# BMS.net
KiCad netlist of a schematic drawn in EAGLE
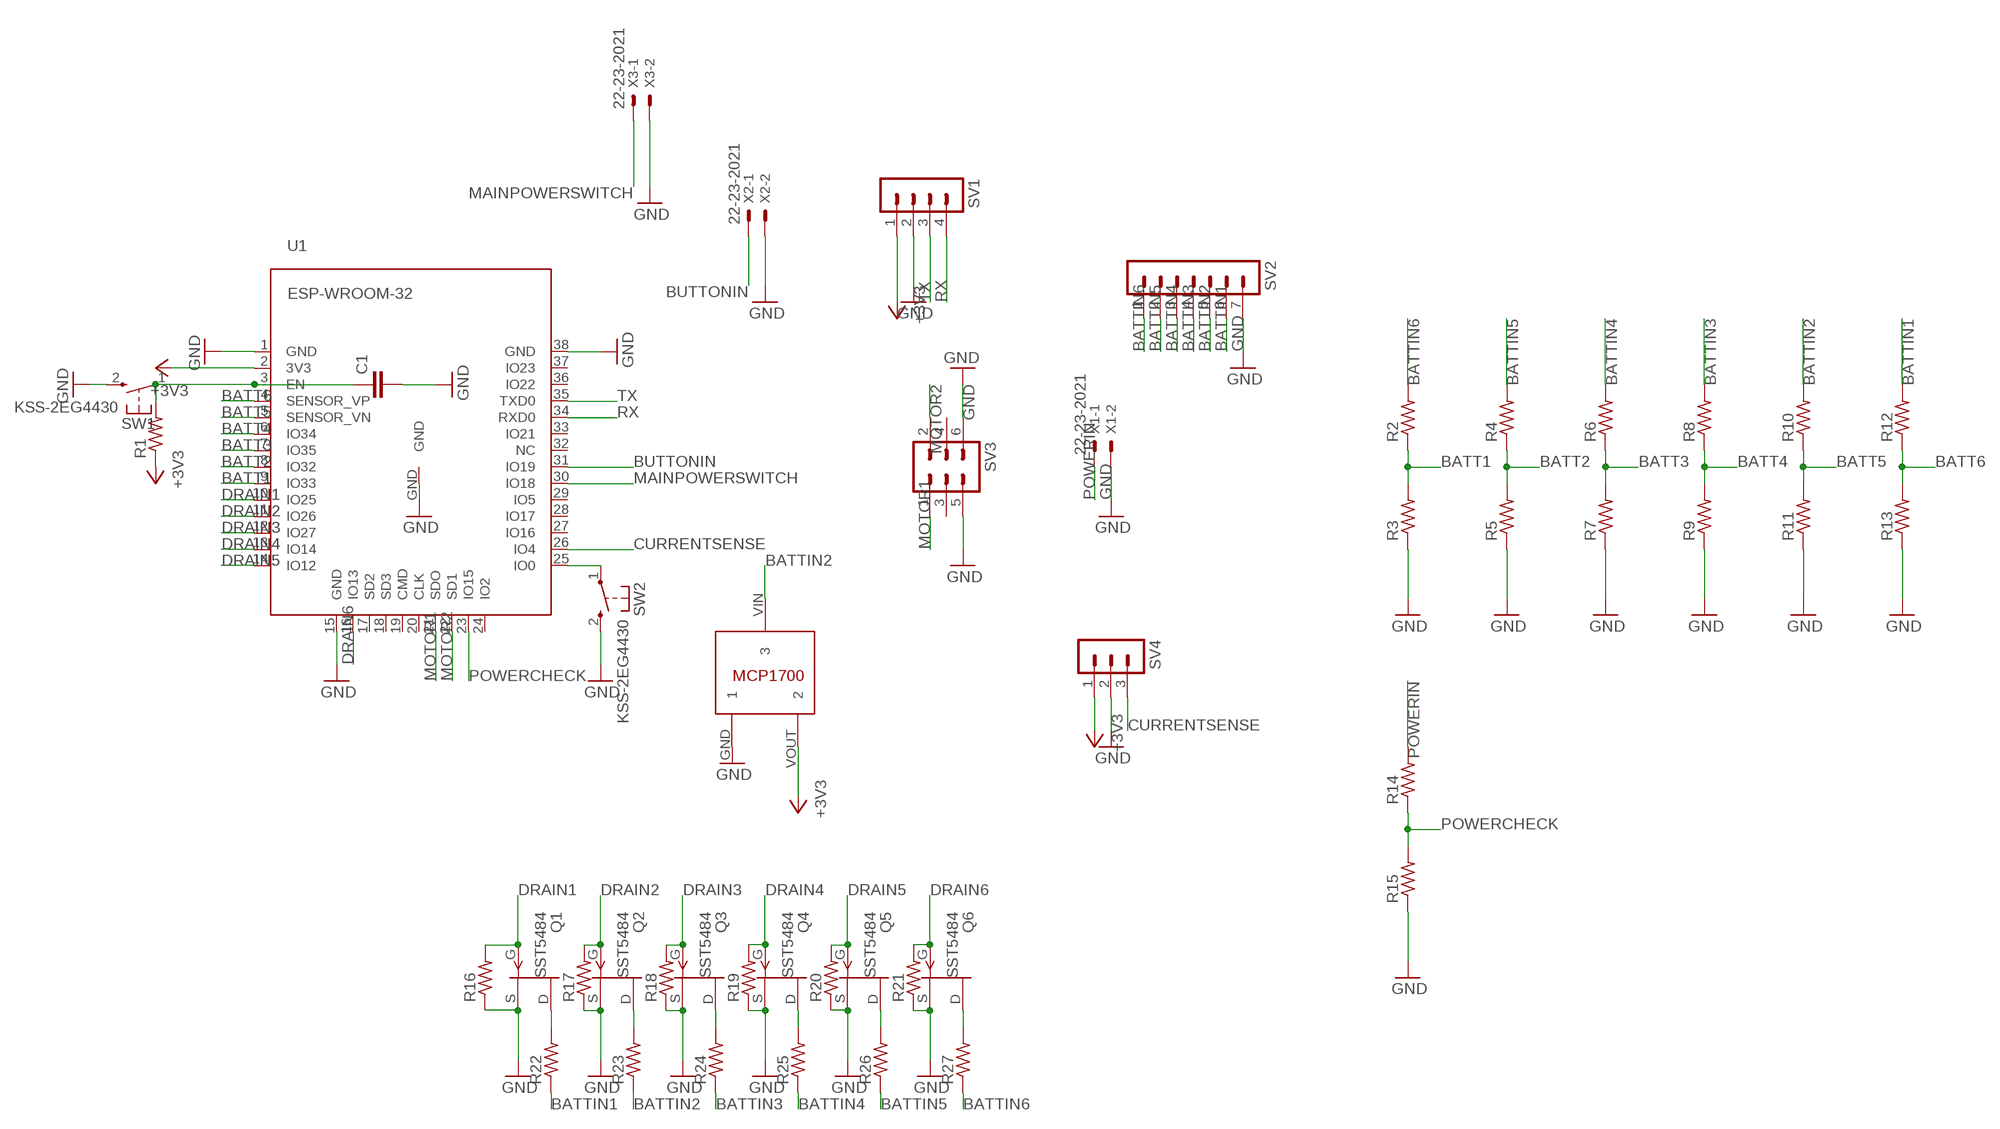
[diagram p0: schematic, sheet 1]

(export (version "E")
  (design (tool "Eeschema 10.0.6"))
  (components
    (comp (ref "C1")
      (value "C-EUC0402")
      (footprint "eagle-import:C0402")
      (libsource (lib "eagle-import") (part "C-EUC0402"))
    )
    (comp (ref "Q1")
      (value "SST5484")
      (footprint "eagle-import:SOT23")
      (libsource (lib "eagle-import") (part "?548SST4"))
    )
    (comp (ref "Q2")
      (value "SST5484")
      (footprint "eagle-import:SOT23")
      (libsource (lib "eagle-import") (part "?548SST4"))
    )
    (comp (ref "Q3")
      (value "SST5484")
      (footprint "eagle-import:SOT23")
      (libsource (lib "eagle-import") (part "?548SST4"))
    )
    (comp (ref "Q4")
      (value "SST5484")
      (footprint "eagle-import:SOT23")
      (libsource (lib "eagle-import") (part "?548SST4"))
    )
    (comp (ref "Q5")
      (value "SST5484")
      (footprint "eagle-import:SOT23")
      (libsource (lib "eagle-import") (part "?548SST4"))
    )
    (comp (ref "Q6")
      (value "SST5484")
      (footprint "eagle-import:SOT23")
      (libsource (lib "eagle-import") (part "?548SST4"))
    )
    (comp (ref "R1")
      (value "R-US_R0805")
      (footprint "eagle-import:R0805")
      (libsource (lib "eagle-import") (part "R-US_R0805"))
    )
    (comp (ref "R2")
      (value "R-US_M0805")
      (footprint "eagle-import:M0805")
      (libsource (lib "eagle-import") (part "resistor_348_R-US_M0805"))
    )
    (comp (ref "R3")
      (value "R-US_M0805")
      (footprint "eagle-import:M0805")
      (libsource (lib "eagle-import") (part "resistor_348_R-US_M0805"))
    )
    (comp (ref "R4")
      (value "R-US_M0805")
      (footprint "eagle-import:M0805")
      (libsource (lib "eagle-import") (part "resistor_348_R-US_M0805"))
    )
    (comp (ref "R5")
      (value "R-US_M0805")
      (footprint "eagle-import:M0805")
      (libsource (lib "eagle-import") (part "resistor_348_R-US_M0805"))
    )
    (comp (ref "R6")
      (value "R-US_M0805")
      (footprint "eagle-import:M0805")
      (libsource (lib "eagle-import") (part "resistor_348_R-US_M0805"))
    )
    (comp (ref "R7")
      (value "R-US_M0805")
      (footprint "eagle-import:M0805")
      (libsource (lib "eagle-import") (part "resistor_348_R-US_M0805"))
    )
    (comp (ref "R8")
      (value "R-US_M0805")
      (footprint "eagle-import:M0805")
      (libsource (lib "eagle-import") (part "resistor_348_R-US_M0805"))
    )
    (comp (ref "R9")
      (value "R-US_M0805")
      (footprint "eagle-import:M0805")
      (libsource (lib "eagle-import") (part "resistor_348_R-US_M0805"))
    )
    (comp (ref "R10")
      (value "R-US_M0805")
      (footprint "eagle-import:M0805")
      (libsource (lib "eagle-import") (part "resistor_348_R-US_M0805"))
    )
    (comp (ref "R11")
      (value "R-US_M0805")
      (footprint "eagle-import:M0805")
      (libsource (lib "eagle-import") (part "resistor_348_R-US_M0805"))
    )
    (comp (ref "R12")
      (value "R-US_M0805")
      (footprint "eagle-import:M0805")
      (libsource (lib "eagle-import") (part "resistor_348_R-US_M0805"))
    )
    (comp (ref "R13")
      (value "R-US_M0805")
      (footprint "eagle-import:M0805")
      (libsource (lib "eagle-import") (part "resistor_348_R-US_M0805"))
    )
    (comp (ref "R14")
      (value "R-US_M0805")
      (footprint "eagle-import:M0805")
      (libsource (lib "eagle-import") (part "resistor_348_R-US_M0805"))
    )
    (comp (ref "R15")
      (value "R-US_M0805")
      (footprint "eagle-import:M0805")
      (libsource (lib "eagle-import") (part "resistor_348_R-US_M0805"))
    )
    (comp (ref "R16")
      (value "R-US_M0805")
      (footprint "eagle-import:M0805")
      (libsource (lib "eagle-import") (part "R-US_M0805"))
    )
    (comp (ref "R17")
      (value "R-US_M0805")
      (footprint "eagle-import:M0805")
      (libsource (lib "eagle-import") (part "R-US_M0805"))
    )
    (comp (ref "R18")
      (value "R-US_M0805")
      (footprint "eagle-import:M0805")
      (libsource (lib "eagle-import") (part "R-US_M0805"))
    )
    (comp (ref "R19")
      (value "R-US_M0805")
      (footprint "eagle-import:M0805")
      (libsource (lib "eagle-import") (part "R-US_M0805"))
    )
    (comp (ref "R20")
      (value "R-US_M0805")
      (footprint "eagle-import:M0805")
      (libsource (lib "eagle-import") (part "R-US_M0805"))
    )
    (comp (ref "R21")
      (value "R-US_M0805")
      (footprint "eagle-import:M0805")
      (libsource (lib "eagle-import") (part "R-US_M0805"))
    )
    (comp (ref "R22")
      (value "R-US_M0805")
      (footprint "eagle-import:M0805")
      (libsource (lib "eagle-import") (part "R-US_M0805"))
    )
    (comp (ref "R23")
      (value "R-US_M0805")
      (footprint "eagle-import:M0805")
      (libsource (lib "eagle-import") (part "R-US_M0805"))
    )
    (comp (ref "R24")
      (value "R-US_M0805")
      (footprint "eagle-import:M0805")
      (libsource (lib "eagle-import") (part "R-US_M0805"))
    )
    (comp (ref "R25")
      (value "R-US_M0805")
      (footprint "eagle-import:M0805")
      (libsource (lib "eagle-import") (part "R-US_M0805"))
    )
    (comp (ref "R26")
      (value "R-US_M0805")
      (footprint "eagle-import:M0805")
      (libsource (lib "eagle-import") (part "R-US_M0805"))
    )
    (comp (ref "R27")
      (value "R-US_M0805")
      (footprint "eagle-import:M0805")
      (libsource (lib "eagle-import") (part "R-US_M0805"))
    )
    (comp (ref "SV1")
      (value "MA04-1")
      (footprint "eagle-import:MA04-1")
      (libsource (lib "eagle-import") (part "MA04-1"))
    )
    (comp (ref "SV2")
      (value "MA07-1")
      (footprint "eagle-import:MA07-1")
      (libsource (lib "eagle-import") (part "MA07-1"))
    )
    (comp (ref "SV3")
      (value "MA03-2")
      (footprint "eagle-import:MA03-2")
      (libsource (lib "eagle-import") (part "MA03-2"))
    )
    (comp (ref "SV4")
      (value "MA03-1")
      (footprint "eagle-import:MA03-1")
      (libsource (lib "eagle-import") (part "MA03-1"))
    )
    (comp (ref "SW1")
      (value "KSS-2EG4430")
      (footprint "eagle-import:KSS-2EG4430")
      (libsource (lib "eagle-import") (part "KSS-2EG4430"))
    )
    (comp (ref "SW2")
      (value "KSS-2EG4430")
      (footprint "eagle-import:KSS-2EG4430")
      (libsource (lib "eagle-import") (part "KSS-2EG4430"))
    )
    (comp (ref "U$1")
      (value "MCP1700T-3302E/TT")
      (footprint "eagle-import:MCP1700T-3302E_TT")
      (libsource (lib "eagle-import") (part "MCP1700T-3302E/TT"))
    )
    (comp (ref "U1")
      (value "ESP-WROOM-32")
      (footprint "eagle-import:ESP-WROOM-32")
      (libsource (lib "eagle-import") (part "ESP-WROOM-32"))
    )
    (comp (ref "X1")
      (value "22-23-2021")
      (footprint "eagle-import:22-23-2021")
      (fields (field (name "MF") "MOLEX"))
      (libsource (lib "eagle-import") (part "22-23-2021"))
    )
    (comp (ref "X2")
      (value "22-23-2021")
      (footprint "eagle-import:22-23-2021")
      (fields (field (name "MF") "MOLEX"))
      (libsource (lib "eagle-import") (part "22-23-2021"))
    )
    (comp (ref "X3")
      (value "22-23-2021")
      (footprint "eagle-import:22-23-2021")
      (fields (field (name "MF") "MOLEX"))
      (libsource (lib "eagle-import") (part "22-23-2021"))
    )
  )
  (nets
    (net (code "1") (name "+3V3") (class "Default")
      (node (ref "R1") (pin "1") (pinfunction "1_1") (pintype "passive"))
      (node (ref "SV1") (pin "1") (pinfunction "1_1") (pintype "passive"))
      (node (ref "SV4") (pin "1") (pinfunction "1_1") (pintype "passive"))
      (node (ref "U$1") (pin "VOUT") (pinfunction "2_VOUT") (pintype "bidirectional"))
      (node (ref "U1") (pin "2") (pinfunction "3V3_2") (pintype "bidirectional"))
    )
    (net (code "2") (name "/BATT1") (class "Default")
      (node (ref "R2") (pin "1") (pinfunction "1_1") (pintype "passive"))
      (node (ref "R3") (pin "2") (pinfunction "2_2") (pintype "passive"))
      (node (ref "U1") (pin "9") (pinfunction "IO33_9") (pintype "bidirectional"))
    )
    (net (code "3") (name "/BATT2") (class "Default")
      (node (ref "R4") (pin "1") (pinfunction "1_1") (pintype "passive"))
      (node (ref "R5") (pin "2") (pinfunction "2_2") (pintype "passive"))
      (node (ref "U1") (pin "8") (pinfunction "IO32_8") (pintype "bidirectional"))
    )
    (net (code "4") (name "/BATT3") (class "Default")
      (node (ref "R6") (pin "1") (pinfunction "1_1") (pintype "passive"))
      (node (ref "R7") (pin "2") (pinfunction "2_2") (pintype "passive"))
      (node (ref "U1") (pin "7") (pinfunction "IO35_7") (pintype "bidirectional"))
    )
    (net (code "5") (name "/BATT4") (class "Default")
      (node (ref "R8") (pin "1") (pinfunction "1_1") (pintype "passive"))
      (node (ref "R9") (pin "2") (pinfunction "2_2") (pintype "passive"))
      (node (ref "U1") (pin "6") (pinfunction "IO34_6") (pintype "bidirectional"))
    )
    (net (code "6") (name "/BATT5") (class "Default")
      (node (ref "R10") (pin "1") (pinfunction "1_1") (pintype "passive"))
      (node (ref "R11") (pin "2") (pinfunction "2_2") (pintype "passive"))
      (node (ref "U1") (pin "5") (pinfunction "SENSOR_VN_5") (pintype "bidirectional"))
    )
    (net (code "7") (name "/BATT6") (class "Default")
      (node (ref "R12") (pin "1") (pinfunction "1_1") (pintype "passive"))
      (node (ref "R13") (pin "2") (pinfunction "2_2") (pintype "passive"))
      (node (ref "U1") (pin "4") (pinfunction "SENSOR_VP_4") (pintype "bidirectional"))
    )
    (net (code "8") (name "/BATTIN1") (class "Default")
      (node (ref "R12") (pin "2") (pinfunction "2_2") (pintype "passive"))
      (node (ref "R22") (pin "1") (pinfunction "1_1") (pintype "passive"))
      (node (ref "SV2") (pin "6") (pinfunction "6_6") (pintype "passive"))
    )
    (net (code "9") (name "/BATTIN2") (class "Default")
      (node (ref "R10") (pin "2") (pinfunction "2_2") (pintype "passive"))
      (node (ref "R23") (pin "1") (pinfunction "1_1") (pintype "passive"))
      (node (ref "SV2") (pin "5") (pinfunction "5_5") (pintype "passive"))
      (node (ref "U$1") (pin "VIN") (pinfunction "3_VIN") (pintype "bidirectional"))
    )
    (net (code "10") (name "/BATTIN3") (class "Default")
      (node (ref "R24") (pin "1") (pinfunction "1_1") (pintype "passive"))
      (node (ref "R8") (pin "2") (pinfunction "2_2") (pintype "passive"))
      (node (ref "SV2") (pin "4") (pinfunction "4_4") (pintype "passive"))
    )
    (net (code "11") (name "/BATTIN4") (class "Default")
      (node (ref "R25") (pin "1") (pinfunction "1_1") (pintype "passive"))
      (node (ref "R6") (pin "2") (pinfunction "2_2") (pintype "passive"))
      (node (ref "SV2") (pin "3") (pinfunction "3_3") (pintype "passive"))
    )
    (net (code "12") (name "/BATTIN5") (class "Default")
      (node (ref "R26") (pin "1") (pinfunction "1_1") (pintype "passive"))
      (node (ref "R4") (pin "2") (pinfunction "2_2") (pintype "passive"))
      (node (ref "SV2") (pin "2") (pinfunction "2_2") (pintype "passive"))
    )
    (net (code "13") (name "/BATTIN6") (class "Default")
      (node (ref "R2") (pin "2") (pinfunction "2_2") (pintype "passive"))
      (node (ref "R27") (pin "1") (pinfunction "1_1") (pintype "passive"))
      (node (ref "SV2") (pin "1") (pinfunction "1_1") (pintype "passive"))
    )
    (net (code "14") (name "/BUTTONIN") (class "Default")
      (node (ref "U1") (pin "31") (pinfunction "IO19_31") (pintype "bidirectional"))
      (node (ref "X2") (pin "1") (pinfunction "S_1") (pintype "passive"))
    )
    (net (code "15") (name "/CURRENTSENSE") (class "Default")
      (node (ref "SV4") (pin "3") (pinfunction "3_3") (pintype "passive"))
      (node (ref "U1") (pin "26") (pinfunction "IO4_26") (pintype "bidirectional"))
    )
    (net (code "16") (name "/DRAIN1") (class "Default")
      (node (ref "Q1") (pin "3") (pinfunction "G_3") (pintype "passive"))
      (node (ref "R16") (pin "2") (pinfunction "2_2") (pintype "passive"))
      (node (ref "U1") (pin "10") (pinfunction "IO25_10") (pintype "bidirectional"))
    )
    (net (code "17") (name "/DRAIN2") (class "Default")
      (node (ref "Q2") (pin "3") (pinfunction "G_3") (pintype "passive"))
      (node (ref "R17") (pin "2") (pinfunction "2_2") (pintype "passive"))
      (node (ref "U1") (pin "11") (pinfunction "IO26_11") (pintype "bidirectional"))
    )
    (net (code "18") (name "/DRAIN3") (class "Default")
      (node (ref "Q3") (pin "3") (pinfunction "G_3") (pintype "passive"))
      (node (ref "R18") (pin "2") (pinfunction "2_2") (pintype "passive"))
      (node (ref "U1") (pin "12") (pinfunction "IO27_12") (pintype "bidirectional"))
    )
    (net (code "19") (name "/DRAIN4") (class "Default")
      (node (ref "Q4") (pin "3") (pinfunction "G_3") (pintype "passive"))
      (node (ref "R19") (pin "2") (pinfunction "2_2") (pintype "passive"))
      (node (ref "U1") (pin "13") (pinfunction "IO14_13") (pintype "bidirectional"))
    )
    (net (code "20") (name "/DRAIN5") (class "Default")
      (node (ref "Q5") (pin "3") (pinfunction "G_3") (pintype "passive"))
      (node (ref "R20") (pin "2") (pinfunction "2_2") (pintype "passive"))
      (node (ref "U1") (pin "14") (pinfunction "IO12_14") (pintype "bidirectional"))
    )
    (net (code "21") (name "/DRAIN6") (class "Default")
      (node (ref "Q6") (pin "3") (pinfunction "G_3") (pintype "passive"))
      (node (ref "R21") (pin "2") (pinfunction "2_2") (pintype "passive"))
      (node (ref "U1") (pin "16") (pinfunction "IO13_16") (pintype "bidirectional"))
    )
    (net (code "22") (name "/MAINPOWERSWITCH") (class "Default")
      (node (ref "U1") (pin "30") (pinfunction "IO18_30") (pintype "bidirectional"))
      (node (ref "X3") (pin "1") (pinfunction "S_1") (pintype "passive"))
    )
    (net (code "23") (name "/MOTOR1") (class "Default")
      (node (ref "SV3") (pin "1") (pinfunction "1_1") (pintype "passive"))
      (node (ref "U1") (pin "21") (pinfunction "SDO_21") (pintype "bidirectional"))
    )
    (net (code "24") (name "/MOTOR2") (class "Default")
      (node (ref "SV3") (pin "2") (pinfunction "2_2") (pintype "passive"))
      (node (ref "U1") (pin "22") (pinfunction "SD1_22") (pintype "bidirectional"))
    )
    (net (code "25") (name "/POWERCHECK") (class "Default")
      (node (ref "R14") (pin "1") (pinfunction "1_1") (pintype "passive"))
      (node (ref "R15") (pin "2") (pinfunction "2_2") (pintype "passive"))
      (node (ref "U1") (pin "23") (pinfunction "IO15_23") (pintype "bidirectional"))
    )
    (net (code "26") (name "/POWERIN") (class "Default")
      (node (ref "R14") (pin "2") (pinfunction "2_2") (pintype "passive"))
      (node (ref "X1") (pin "1") (pinfunction "S_1") (pintype "passive"))
    )
    (net (code "27") (name "/RX") (class "Default")
      (node (ref "SV1") (pin "4") (pinfunction "4_4") (pintype "passive"))
      (node (ref "U1") (pin "34") (pinfunction "RXD0_34") (pintype "bidirectional"))
    )
    (net (code "28") (name "/TX") (class "Default")
      (node (ref "SV1") (pin "3") (pinfunction "3_3") (pintype "passive"))
      (node (ref "U1") (pin "35") (pinfunction "TXD0_35") (pintype "bidirectional"))
    )
    (net (code "29") (name "GND") (class "Default")
      (node (ref "C1") (pin "2") (pinfunction "2_2") (pintype "passive"))
      (node (ref "Q1") (pin "2") (pinfunction "S_2") (pintype "passive"))
      (node (ref "Q2") (pin "2") (pinfunction "S_2") (pintype "passive"))
      (node (ref "Q3") (pin "2") (pinfunction "S_2") (pintype "passive"))
      (node (ref "Q4") (pin "2") (pinfunction "S_2") (pintype "passive"))
      (node (ref "Q5") (pin "2") (pinfunction "S_2") (pintype "passive"))
      (node (ref "Q6") (pin "2") (pinfunction "S_2") (pintype "passive"))
      (node (ref "R11") (pin "1") (pinfunction "1_1") (pintype "passive"))
      (node (ref "R13") (pin "1") (pinfunction "1_1") (pintype "passive"))
      (node (ref "R15") (pin "1") (pinfunction "1_1") (pintype "passive"))
      (node (ref "R16") (pin "1") (pinfunction "1_1") (pintype "passive"))
      (node (ref "R17") (pin "1") (pinfunction "1_1") (pintype "passive"))
      (node (ref "R18") (pin "1") (pinfunction "1_1") (pintype "passive"))
      (node (ref "R19") (pin "1") (pinfunction "1_1") (pintype "passive"))
      (node (ref "R20") (pin "1") (pinfunction "1_1") (pintype "passive"))
      (node (ref "R21") (pin "1") (pinfunction "1_1") (pintype "passive"))
      (node (ref "R3") (pin "1") (pinfunction "1_1") (pintype "passive"))
      (node (ref "R5") (pin "1") (pinfunction "1_1") (pintype "passive"))
      (node (ref "R7") (pin "1") (pinfunction "1_1") (pintype "passive"))
      (node (ref "R9") (pin "1") (pinfunction "1_1") (pintype "passive"))
      (node (ref "SV1") (pin "2") (pinfunction "2_2") (pintype "passive"))
      (node (ref "SV2") (pin "7") (pinfunction "7_7") (pintype "passive"))
      (node (ref "SV3") (pin "5") (pinfunction "5_5") (pintype "passive"))
      (node (ref "SV3") (pin "6") (pinfunction "6_6") (pintype "passive"))
      (node (ref "SV4") (pin "2") (pinfunction "2_2") (pintype "passive"))
      (node (ref "SW1") (pin "2") (pinfunction "S_2") (pintype "passive"))
      (node (ref "SW2") (pin "2") (pinfunction "S_2") (pintype "passive"))
      (node (ref "U$1") (pin "GND") (pinfunction "1_GND") (pintype "bidirectional"))
      (node (ref "U1") (pin "1") (pinfunction "GND_1") (pintype "bidirectional"))
      (node (ref "U1") (pin "15") (pinfunction "GND_15") (pintype "bidirectional"))
      (node (ref "U1") (pin "38") (pinfunction "GND_38") (pintype "bidirectional"))
      (node (ref "U1") (pin "GND") (pinfunction "GND_GND") (pintype "bidirectional"))
      (node (ref "X1") (pin "2") (pinfunction "S_2") (pintype "passive"))
      (node (ref "X2") (pin "2") (pinfunction "S_2") (pintype "passive"))
      (node (ref "X3") (pin "2") (pinfunction "S_2") (pintype "passive"))
    )
    (net (code "30") (name "Net-(Q1-D)") (class "Default")
      (node (ref "Q1") (pin "1") (pinfunction "D_1") (pintype "passive"))
      (node (ref "R22") (pin "2") (pinfunction "2_2") (pintype "passive"))
    )
    (net (code "31") (name "Net-(Q2-D)") (class "Default")
      (node (ref "Q2") (pin "1") (pinfunction "D_1") (pintype "passive"))
      (node (ref "R23") (pin "2") (pinfunction "2_2") (pintype "passive"))
    )
    (net (code "32") (name "Net-(Q3-D)") (class "Default")
      (node (ref "Q3") (pin "1") (pinfunction "D_1") (pintype "passive"))
      (node (ref "R24") (pin "2") (pinfunction "2_2") (pintype "passive"))
    )
    (net (code "33") (name "Net-(Q4-D)") (class "Default")
      (node (ref "Q4") (pin "1") (pinfunction "D_1") (pintype "passive"))
      (node (ref "R25") (pin "2") (pinfunction "2_2") (pintype "passive"))
    )
    (net (code "34") (name "Net-(Q5-D)") (class "Default")
      (node (ref "Q5") (pin "1") (pinfunction "D_1") (pintype "passive"))
      (node (ref "R26") (pin "2") (pinfunction "2_2") (pintype "passive"))
    )
    (net (code "35") (name "Net-(Q6-D)") (class "Default")
      (node (ref "Q6") (pin "1") (pinfunction "D_1") (pintype "passive"))
      (node (ref "R27") (pin "2") (pinfunction "2_2") (pintype "passive"))
    )
    (net (code "36") (name "Net-(SW1-P)") (class "Default")
      (node (ref "C1") (pin "1") (pinfunction "1_1") (pintype "passive"))
      (node (ref "R1") (pin "2") (pinfunction "2_2") (pintype "passive"))
      (node (ref "SW1") (pin "1") (pinfunction "P_1") (pintype "passive"))
      (node (ref "U1") (pin "3") (pinfunction "EN_3") (pintype "bidirectional"))
    )
    (net (code "37") (name "Net-(SW2-P)") (class "Default")
      (node (ref "SW2") (pin "1") (pinfunction "P_1") (pintype "passive"))
      (node (ref "U1") (pin "25") (pinfunction "IO0_25") (pintype "bidirectional"))
    )
    (net (code "38") (name "unconnected-(SV3-Pad3)") (class "Default")
      (node (ref "SV3") (pin "3") (pinfunction "3_3") (pintype "passive"))
    )
    (net (code "39") (name "unconnected-(SV3-Pad4)") (class "Default")
      (node (ref "SV3") (pin "4") (pinfunction "4_4") (pintype "passive"))
    )
    (net (code "40") (name "unconnected-(U1-CLK-Pad20)") (class "Default")
      (node (ref "U1") (pin "20") (pinfunction "CLK_20") (pintype "bidirectional"))
    )
    (net (code "41") (name "unconnected-(U1-CMD-Pad19)") (class "Default")
      (node (ref "U1") (pin "19") (pinfunction "CMD_19") (pintype "bidirectional"))
    )
    (net (code "42") (name "unconnected-(U1-IO2-Pad24)") (class "Default")
      (node (ref "U1") (pin "24") (pinfunction "IO2_24") (pintype "bidirectional"))
    )
    (net (code "43") (name "unconnected-(U1-IO5-Pad29)") (class "Default")
      (node (ref "U1") (pin "29") (pinfunction "IO5_29") (pintype "bidirectional"))
    )
    (net (code "44") (name "unconnected-(U1-IO16-Pad27)") (class "Default")
      (node (ref "U1") (pin "27") (pinfunction "IO16_27") (pintype "bidirectional"))
    )
    (net (code "45") (name "unconnected-(U1-IO17-Pad28)") (class "Default")
      (node (ref "U1") (pin "28") (pinfunction "IO17_28") (pintype "bidirectional"))
    )
    (net (code "46") (name "unconnected-(U1-IO21-Pad33)") (class "Default")
      (node (ref "U1") (pin "33") (pinfunction "IO21_33") (pintype "bidirectional"))
    )
    (net (code "47") (name "unconnected-(U1-IO22-Pad36)") (class "Default")
      (node (ref "U1") (pin "36") (pinfunction "IO22_36") (pintype "bidirectional"))
    )
    (net (code "48") (name "unconnected-(U1-IO23-Pad37)") (class "Default")
      (node (ref "U1") (pin "37") (pinfunction "IO23_37") (pintype "bidirectional"))
    )
    (net (code "49") (name "unconnected-(U1-NC-Pad32)") (class "Default")
      (node (ref "U1") (pin "32") (pinfunction "NC_32") (pintype "bidirectional"))
    )
    (net (code "50") (name "unconnected-(U1-SD2-Pad17)") (class "Default")
      (node (ref "U1") (pin "17") (pinfunction "SD2_17") (pintype "bidirectional"))
    )
    (net (code "51") (name "unconnected-(U1-SD3-Pad18)") (class "Default")
      (node (ref "U1") (pin "18") (pinfunction "SD3_18") (pintype "bidirectional"))
    )
  )
)
